# powerpump.net
KiCad netlist of a schematic drawn in Altium Designer
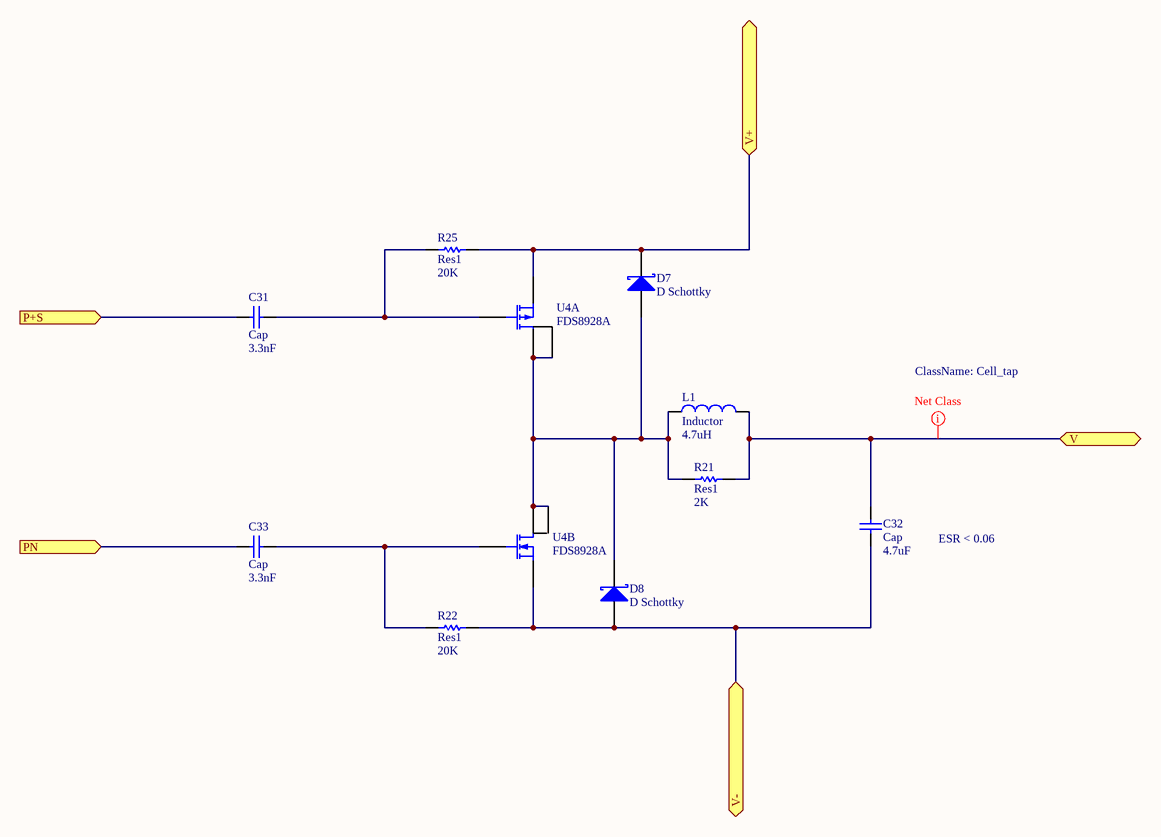
[diagram p0: powerpump.SchDoc]

(export (version "E")
  (design (tool "Eeschema 10.0.6"))
  (components
    (comp (ref "C31")
      (value "Cap")
      (footprint "C0805")
      (description "Capacitor")
      (fields (field (name "ALTIUM_VALUE") "3.3nF") (field (name "PUBLISHER") "Altium Limited"))
      (libsource (lib "Miscellaneous Devices") (part "Cap"))
    )
    (comp (ref "C32")
      (value "Cap")
      (footprint "C0805")
      (description "Capacitor")
      (fields (field (name "ALTIUM_VALUE") "4.7uF") (field (name "PUBLISHER") "Altium Limited"))
      (libsource (lib "Miscellaneous Devices") (part "Cap"))
    )
    (comp (ref "C33")
      (value "Cap")
      (footprint "C0805")
      (description "Capacitor")
      (fields (field (name "ALTIUM_VALUE") "3.3nF") (field (name "PUBLISHER") "Altium Limited"))
      (libsource (lib "Miscellaneous Devices") (part "Cap"))
    )
    (comp (ref "D7")
      (value "D Schottky")
      (footprint "B0520LW")
      (description "Schottky Diode")
      (fields (field (name "PUBLISHER") "Altium Limited"))
      (libsource (lib "Miscellaneous Devices") (part "D Schottky"))
    )
    (comp (ref "D8")
      (value "D Schottky")
      (footprint "B0520LW")
      (description "Schottky Diode")
      (fields (field (name "PUBLISHER") "Altium Limited"))
      (libsource (lib "Miscellaneous Devices") (part "D Schottky"))
    )
    (comp (ref "L1")
      (value "Inductor")
      (footprint "LQH44P")
      (fields (field (name "ALTIUM_VALUE") "4.7uH") (field (name "PUBLISHER") "Altium Limited"))
      (libsource (lib "Miscellaneous Devices") (part "Inductor"))
    )
    (comp (ref "R21")
      (value "Res1")
      (footprint "R0603")
      (description "Resistor")
      (fields (field (name "ALTIUM_VALUE") "2K") (field (name "PUBLISHER") "Altium Limited"))
      (libsource (lib "Miscellaneous Devices") (part "Res1"))
    )
    (comp (ref "R22")
      (value "Res1")
      (footprint "R0603")
      (description "Resistor")
      (fields (field (name "ALTIUM_VALUE") "20K") (field (name "PUBLISHER") "Altium Limited"))
      (libsource (lib "Miscellaneous Devices") (part "Res1"))
    )
    (comp (ref "R25")
      (value "Res1")
      (footprint "R0603")
      (description "Resistor")
      (fields (field (name "ALTIUM_VALUE") "20K") (field (name "PUBLISHER") "Altium Limited"))
      (libsource (lib "Miscellaneous Devices") (part "Res1"))
    )
    (comp (ref "U4")
      (value "FDS8928A")
      (footprint "FDS8928A")
      (description "MOSFET, DUAL, NP, SMD, 8-SOIC")
      (libsource (lib "FDS8928A (N-P dual MOSFET)") (part "FDS8928A"))
    )
  )
  (nets
    (net (code "1") (name "/P+S") (class "Default")
      (node (ref "C31") (pin "1") (pinfunction "1_1") (pintype "passive"))
    )
    (net (code "2") (name "/PN") (class "Default")
      (node (ref "C33") (pin "1") (pinfunction "1_1") (pintype "passive"))
    )
    (net (code "3") (name "/V") (class "Default")
      (node (ref "C32") (pin "1") (pinfunction "1_1") (pintype "passive"))
      (node (ref "L1") (pin "2") (pinfunction "2_2") (pintype "passive"))
      (node (ref "R21") (pin "2") (pinfunction "2_2") (pintype "passive"))
    )
    (net (code "4") (name "/V+") (class "Default")
      (node (ref "D7") (pin "2") (pinfunction "K_2") (pintype "passive"))
      (node (ref "R25") (pin "2") (pinfunction "2_2") (pintype "passive"))
      (node (ref "U4") (pin "3") (pinfunction "S_P_3") (pintype "passive"))
    )
    (net (code "5") (name "/V-") (class "Default")
      (node (ref "C32") (pin "2") (pinfunction "2_2") (pintype "passive"))
      (node (ref "D8") (pin "1") (pinfunction "A_1") (pintype "passive"))
      (node (ref "R22") (pin "2") (pinfunction "2_2") (pintype "passive"))
      (node (ref "U4") (pin "1") (pinfunction "S_N_1") (pintype "passive"))
    )
    (net (code "6") (name "Net-(D7-A)") (class "Default")
      (node (ref "D7") (pin "1") (pinfunction "A_1") (pintype "passive"))
      (node (ref "D8") (pin "2") (pinfunction "K_2") (pintype "passive"))
      (node (ref "L1") (pin "1") (pinfunction "1_1") (pintype "passive"))
      (node (ref "R21") (pin "1") (pinfunction "1_1") (pintype "passive"))
      (node (ref "U4") (pin "5") (pinfunction "D_P_5") (pintype "passive"))
      (node (ref "U4") (pin "6") (pinfunction "D_N_6") (pintype "passive"))
      (node (ref "U4") (pin "7") (pinfunction "D_N_7") (pintype "passive"))
      (node (ref "U4") (pin "8") (pinfunction "D_N_8") (pintype "passive"))
    )
    (net (code "7") (name "Net-(U4A-G_P)") (class "Default")
      (node (ref "C31") (pin "2") (pinfunction "2_2") (pintype "passive"))
      (node (ref "R25") (pin "1") (pinfunction "1_1") (pintype "passive"))
      (node (ref "U4") (pin "4") (pinfunction "G_P_4") (pintype "passive"))
    )
    (net (code "8") (name "Net-(U4B-G_N)") (class "Default")
      (node (ref "C33") (pin "2") (pinfunction "2_2") (pintype "passive"))
      (node (ref "R22") (pin "1") (pinfunction "1_1") (pintype "passive"))
      (node (ref "U4") (pin "2") (pinfunction "G_N_2") (pintype "passive"))
    )
  )
)
